# sb-sonata-fpgaio1.net
KiCad netlist of a schematic drawn in Altium Designer
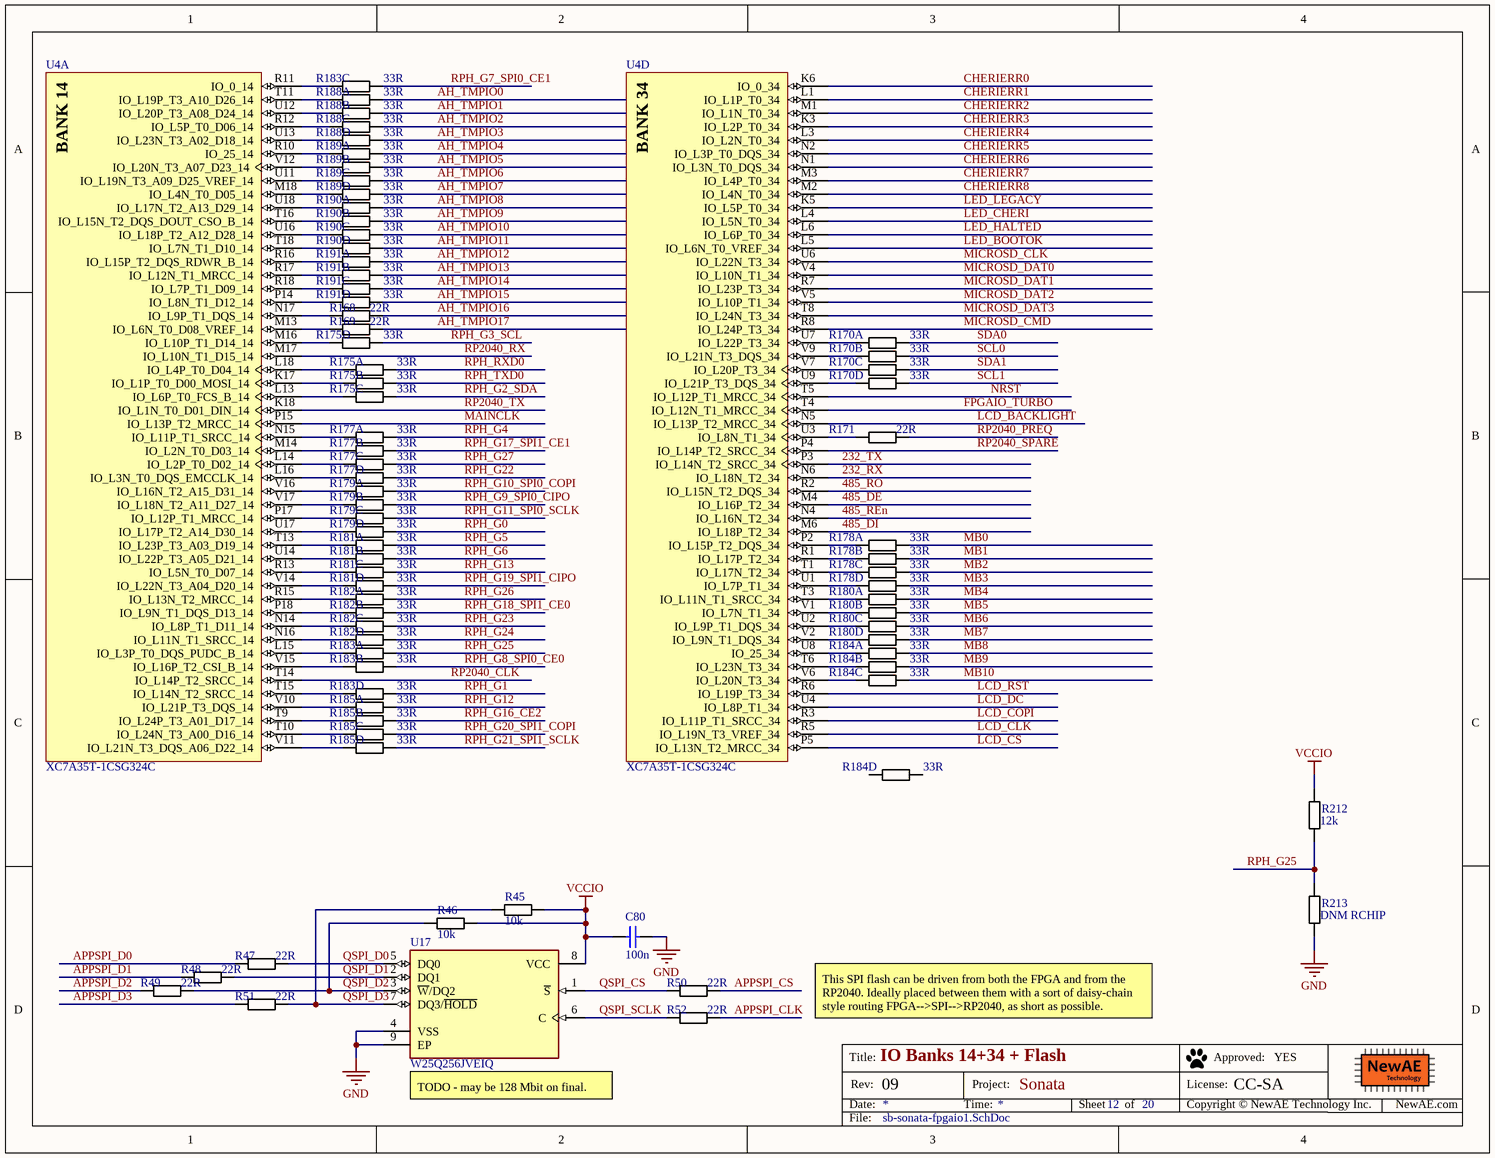
[diagram p0: sb-sonata-fpgaio1.SchDoc]

(export (version "E")
  (design (tool "Eeschema 10.0.6"))
  (components
    (comp (ref "C80")
      (value "100n")
      (footprint "CAPC0402_M")
      (description "100n, 0402")
      (fields (field (name "PART NUMBER") "CCHIP-100n-0402"))
      (libsource (lib "NewAE_AltiumLib") (part "CAP"))
    )
    (comp (ref "R45")
      (value "10k")
      (footprint "RESC1005X40N")
      (description "10k res, 0402, 1%, 1/16W")
      (fields (field (name "PART NUMBER") "RCHIP-10K-0402") (field (name "TOLERANCE") "1%"))
      (libsource (lib "") (part "RES-EU_1"))
    )
    (comp (ref "R46")
      (value "10k")
      (footprint "RESC1005X40N")
      (description "10k res, 0402, 1%, 1/16W")
      (fields (field (name "PART NUMBER") "RCHIP-10K-0402") (field (name "TOLERANCE") "1%"))
      (libsource (lib "") (part "RES-EU_1"))
    )
    (comp (ref "R47")
      (value "22R")
      (footprint "RESC1005X40N")
      (description "22R res, 0402, 1%, 1/16W")
      (fields (field (name "PART NUMBER") "RCHIP-22R-0402") (field (name "TOLERANCE") "1%"))
      (libsource (lib "NewAE_AltiumLib") (part "RES-EU"))
    )
    (comp (ref "R48")
      (value "22R")
      (footprint "RESC1005X40N")
      (description "22R res, 0402, 1%, 1/16W")
      (fields (field (name "PART NUMBER") "RCHIP-22R-0402") (field (name "TOLERANCE") "1%"))
      (libsource (lib "NewAE_AltiumLib") (part "RES-EU"))
    )
    (comp (ref "R49")
      (value "22R")
      (footprint "RESC1005X40N")
      (description "22R res, 0402, 1%, 1/16W")
      (fields (field (name "PART NUMBER") "RCHIP-22R-0402") (field (name "TOLERANCE") "1%"))
      (libsource (lib "NewAE_AltiumLib") (part "RES-EU"))
    )
    (comp (ref "R50")
      (value "22R")
      (footprint "RESC1005X40N")
      (description "22R res, 0402, 1%, 1/16W")
      (fields (field (name "PART NUMBER") "RCHIP-22R-0402") (field (name "TOLERANCE") "1%"))
      (libsource (lib "NewAE_AltiumLib") (part "RES-EU"))
    )
    (comp (ref "R51")
      (value "22R")
      (footprint "RESC1005X40N")
      (description "22R res, 0402, 1%, 1/16W")
      (fields (field (name "PART NUMBER") "RCHIP-22R-0402") (field (name "TOLERANCE") "1%"))
      (libsource (lib "NewAE_AltiumLib") (part "RES-EU"))
    )
    (comp (ref "R52")
      (value "22R")
      (footprint "RESC1005X40N")
      (description "22R res, 0402, 1%, 1/16W")
      (fields (field (name "PART NUMBER") "RCHIP-22R-0402") (field (name "TOLERANCE") "1%"))
      (libsource (lib "NewAE_AltiumLib") (part "RES-EU"))
    )
    (comp (ref "R168")
      (value "22R")
      (footprint "RESC1005X40N")
      (description "22R res, 0402, 1%, 1/16W")
      (fields (field (name "PART NUMBER") "RCHIP-22R-0402") (field (name "TOLERANCE") "1%"))
      (libsource (lib "NewAE_AltiumLib") (part "RES-EU"))
    )
    (comp (ref "R169")
      (value "22R")
      (footprint "RESC1005X40N")
      (description "22R res, 0402, 1%, 1/16W")
      (fields (field (name "PART NUMBER") "RCHIP-22R-0402") (field (name "TOLERANCE") "1%"))
      (libsource (lib "NewAE_AltiumLib") (part "RES-EU"))
    )
    (comp (ref "R170")
      (value "33R")
      (footprint "741C083")
      (description "33-ohm, 0.5mm res array")
      (fields (field (name "PART NUMBER") "741C083330JP"))
      (libsource (lib "NewAE_AltiumLib") (part "RES-EU-4ARRAY"))
    )
    (comp (ref "R171")
      (value "22R")
      (footprint "RESC1005X40N")
      (description "22R res, 0402, 1%, 1/16W")
      (fields (field (name "PART NUMBER") "RCHIP-22R-0402") (field (name "TOLERANCE") "1%"))
      (libsource (lib "NewAE_AltiumLib") (part "RES-EU"))
    )
    (comp (ref "R175")
      (value "33R")
      (footprint "741C083")
      (description "33-ohm, 0.5mm res array")
      (fields (field (name "PART NUMBER") "741C083330JP"))
      (libsource (lib "NewAE_AltiumLib") (part "RES-EU-4ARRAY"))
    )
    (comp (ref "R177")
      (value "33R")
      (footprint "741C083")
      (description "33-ohm, 0.5mm res array")
      (fields (field (name "PART NUMBER") "741C083330JP"))
      (libsource (lib "NewAE_AltiumLib") (part "RES-EU-4ARRAY"))
    )
    (comp (ref "R178")
      (value "33R")
      (footprint "741C083")
      (description "33-ohm, 0.5mm res array")
      (fields (field (name "PART NUMBER") "741C083330JP"))
      (libsource (lib "NewAE_AltiumLib") (part "RES-EU-4ARRAY"))
    )
    (comp (ref "R179")
      (value "33R")
      (footprint "741C083")
      (description "33-ohm, 0.5mm res array")
      (fields (field (name "PART NUMBER") "741C083330JP"))
      (libsource (lib "NewAE_AltiumLib") (part "RES-EU-4ARRAY"))
    )
    (comp (ref "R180")
      (value "33R")
      (footprint "741C083")
      (description "33-ohm, 0.5mm res array")
      (fields (field (name "PART NUMBER") "741C083330JP"))
      (libsource (lib "NewAE_AltiumLib") (part "RES-EU-4ARRAY"))
    )
    (comp (ref "R181")
      (value "33R")
      (footprint "741C083")
      (description "33-ohm, 0.5mm res array")
      (fields (field (name "PART NUMBER") "741C083330JP"))
      (libsource (lib "NewAE_AltiumLib") (part "RES-EU-4ARRAY"))
    )
    (comp (ref "R182")
      (value "33R")
      (footprint "741C083")
      (description "33-ohm, 0.5mm res array")
      (fields (field (name "PART NUMBER") "741C083330JP"))
      (libsource (lib "NewAE_AltiumLib") (part "RES-EU-4ARRAY"))
    )
    (comp (ref "R183")
      (value "33R")
      (footprint "741C083")
      (description "33-ohm, 0.5mm res array")
      (fields (field (name "PART NUMBER") "741C083330JP"))
      (libsource (lib "NewAE_AltiumLib") (part "RES-EU-4ARRAY"))
    )
    (comp (ref "R184")
      (value "33R")
      (footprint "741C083")
      (description "33-ohm, 0.5mm res array")
      (fields (field (name "PART NUMBER") "741C083330JP"))
      (libsource (lib "NewAE_AltiumLib") (part "RES-EU-4ARRAY"))
    )
    (comp (ref "R185")
      (value "33R")
      (footprint "741C083")
      (description "33-ohm, 0.5mm res array")
      (fields (field (name "PART NUMBER") "741C083330JP"))
      (libsource (lib "NewAE_AltiumLib") (part "RES-EU-4ARRAY"))
    )
    (comp (ref "R188")
      (value "33R")
      (footprint "741C083")
      (description "33-ohm, 0.5mm res array")
      (fields (field (name "PART NUMBER") "741C083330JP"))
      (libsource (lib "NewAE_AltiumLib") (part "RES-EU-4ARRAY"))
    )
    (comp (ref "R189")
      (value "33R")
      (footprint "741C083")
      (description "33-ohm, 0.5mm res array")
      (fields (field (name "PART NUMBER") "741C083330JP"))
      (libsource (lib "NewAE_AltiumLib") (part "RES-EU-4ARRAY"))
    )
    (comp (ref "R190")
      (value "33R")
      (footprint "741C083")
      (description "33-ohm, 0.5mm res array")
      (fields (field (name "PART NUMBER") "741C083330JP"))
      (libsource (lib "NewAE_AltiumLib") (part "RES-EU-4ARRAY"))
    )
    (comp (ref "R191")
      (value "33R")
      (footprint "741C083")
      (description "33-ohm, 0.5mm res array")
      (fields (field (name "PART NUMBER") "741C083330JP"))
      (libsource (lib "NewAE_AltiumLib") (part "RES-EU-4ARRAY"))
    )
    (comp (ref "R212")
      (value "12k")
      (footprint "RESC1608X55N")
      (description "12k res, 0603, 1%, 1/10W")
      (fields (field (name "PART NUMBER") "RCHIP-12K-0603") (field (name "TOLERANCE") "1%"))
      (libsource (lib "") (part "RES-EU_2"))
    )
    (comp (ref "R213")
      (value "DNM RCHIP")
      (footprint "RESC1608X55N")
      (description "Do Not Mount Resistor")
      (fields (field (name "PART NUMBER") "RCHIP-DNM-0603"))
      (libsource (lib "") (part "RES-EU_2"))
    )
    (comp (ref "U4")
      (value "XC7A35T-1CSG324C")
      (footprint "CSG324")
      (description "Artix-7 FPGA, 210 User I/Os, 0 GTP, 324-Ball BGA, Speed Grade 1, Commercial Grade, Pb-Free")
      (fields (field (name "MANUFACTURER") "Xilinx"))
      (libsource (lib "") (part "XLNX-XC7A35T-CSG324_1"))
    )
    (comp (ref "U17")
      (value "W25Q256JVEIQ")
      (footprint "WSON68_Micron")
      (description "IC FLASH 256M SPI 133MHZ 8WPDFN")
      (libsource (lib "NewAE_AltiumLib") (part "QSPI_WSON"))
    )
  )
  (nets
    (net (code "1") (name "/232_RX") (class "Default")
      (node (ref "U4") (pin "N6") (pinfunction "IO_L18N_T2_34_N6") (pintype "bidirectional"))
    )
    (net (code "2") (name "/232_TX") (class "Default")
      (node (ref "U4") (pin "P3") (pinfunction "IO_L14N_T2_SRCC_34_P3") (pintype "bidirectional"))
    )
    (net (code "3") (name "/485_DE") (class "Default")
      (node (ref "U4") (pin "M4") (pinfunction "IO_L16P_T2_34_M4") (pintype "bidirectional"))
    )
    (net (code "4") (name "/485_DI") (class "Default")
      (node (ref "U4") (pin "M6") (pinfunction "IO_L18P_T2_34_M6") (pintype "bidirectional"))
    )
    (net (code "5") (name "/485_REn") (class "Default")
      (node (ref "U4") (pin "N4") (pinfunction "IO_L16N_T2_34_N4") (pintype "bidirectional"))
    )
    (net (code "6") (name "/485_RO") (class "Default")
      (node (ref "U4") (pin "R2") (pinfunction "IO_L15N_T2_DQS_34_R2") (pintype "bidirectional"))
    )
    (net (code "7") (name "/AH_TMPIO0") (class "Default")
      (node (ref "R188") (pin "1B") (pinfunction "1B_1B") (pintype "passive"))
    )
    (net (code "8") (name "/AH_TMPIO1") (class "Default")
      (node (ref "R188") (pin "2B") (pinfunction "2B_2B") (pintype "passive"))
    )
    (net (code "9") (name "/AH_TMPIO2") (class "Default")
      (node (ref "R188") (pin "3B") (pinfunction "3B_3B") (pintype "passive"))
    )
    (net (code "10") (name "/AH_TMPIO3") (class "Default")
      (node (ref "R188") (pin "4B") (pinfunction "4B_4B") (pintype "passive"))
    )
    (net (code "11") (name "/AH_TMPIO4") (class "Default")
      (node (ref "R189") (pin "1B") (pinfunction "1B_1B") (pintype "passive"))
    )
    (net (code "12") (name "/AH_TMPIO5") (class "Default")
      (node (ref "R189") (pin "2B") (pinfunction "2B_2B") (pintype "passive"))
    )
    (net (code "13") (name "/AH_TMPIO6") (class "Default")
      (node (ref "R189") (pin "3B") (pinfunction "3B_3B") (pintype "passive"))
    )
    (net (code "14") (name "/AH_TMPIO7") (class "Default")
      (node (ref "R189") (pin "4B") (pinfunction "4B_4B") (pintype "passive"))
    )
    (net (code "15") (name "/AH_TMPIO8") (class "Default")
      (node (ref "R190") (pin "1B") (pinfunction "1B_1B") (pintype "passive"))
    )
    (net (code "16") (name "/AH_TMPIO9") (class "Default")
      (node (ref "R190") (pin "2B") (pinfunction "2B_2B") (pintype "passive"))
    )
    (net (code "17") (name "/AH_TMPIO10") (class "Default")
      (node (ref "R190") (pin "3B") (pinfunction "3B_3B") (pintype "passive"))
    )
    (net (code "18") (name "/AH_TMPIO11") (class "Default")
      (node (ref "R190") (pin "4B") (pinfunction "4B_4B") (pintype "passive"))
    )
    (net (code "19") (name "/AH_TMPIO12") (class "Default")
      (node (ref "R191") (pin "1B") (pinfunction "1B_1B") (pintype "passive"))
    )
    (net (code "20") (name "/AH_TMPIO13") (class "Default")
      (node (ref "R191") (pin "2B") (pinfunction "2B_2B") (pintype "passive"))
    )
    (net (code "21") (name "/AH_TMPIO14") (class "Default")
      (node (ref "R191") (pin "3B") (pinfunction "3B_3B") (pintype "passive"))
    )
    (net (code "22") (name "/AH_TMPIO15") (class "Default")
      (node (ref "R191") (pin "4B") (pinfunction "4B_4B") (pintype "passive"))
    )
    (net (code "23") (name "/AH_TMPIO16") (class "Default")
      (node (ref "R168") (pin "2") (pinfunction "2_2") (pintype "passive"))
    )
    (net (code "24") (name "/AH_TMPIO17") (class "Default")
      (node (ref "R169") (pin "2") (pinfunction "2_2") (pintype "passive"))
    )
    (net (code "25") (name "/APPSPI_CLK") (class "Default")
      (node (ref "R52") (pin "2") (pinfunction "2_2") (pintype "passive"))
    )
    (net (code "26") (name "/APPSPI_CS") (class "Default")
      (node (ref "R50") (pin "2") (pinfunction "2_2") (pintype "passive"))
    )
    (net (code "27") (name "/APPSPI_D0") (class "Default")
      (node (ref "R47") (pin "1") (pinfunction "1_1") (pintype "passive"))
    )
    (net (code "28") (name "/APPSPI_D1") (class "Default")
      (node (ref "R48") (pin "1") (pinfunction "1_1") (pintype "passive"))
    )
    (net (code "29") (name "/APPSPI_D2") (class "Default")
      (node (ref "R49") (pin "1") (pinfunction "1_1") (pintype "passive"))
    )
    (net (code "30") (name "/APPSPI_D3") (class "Default")
      (node (ref "R51") (pin "1") (pinfunction "1_1") (pintype "passive"))
    )
    (net (code "31") (name "/CHERIERR0") (class "Default")
      (node (ref "U4") (pin "K6") (pinfunction "IO_0_34_K6") (pintype "bidirectional"))
    )
    (net (code "32") (name "/CHERIERR1") (class "Default")
      (node (ref "U4") (pin "L1") (pinfunction "IO_L1P_T0_34_L1") (pintype "bidirectional"))
    )
    (net (code "33") (name "/CHERIERR2") (class "Default")
      (node (ref "U4") (pin "M1") (pinfunction "IO_L1N_T0_34_M1") (pintype "bidirectional"))
    )
    (net (code "34") (name "/CHERIERR3") (class "Default")
      (node (ref "U4") (pin "K3") (pinfunction "IO_L2P_T0_34_K3") (pintype "bidirectional"))
    )
    (net (code "35") (name "/CHERIERR4") (class "Default")
      (node (ref "U4") (pin "L3") (pinfunction "IO_L2N_T0_34_L3") (pintype "bidirectional"))
    )
    (net (code "36") (name "/CHERIERR5") (class "Default")
      (node (ref "U4") (pin "N2") (pinfunction "IO_L3P_T0_DQS_34_N2") (pintype "bidirectional"))
    )
    (net (code "37") (name "/CHERIERR6") (class "Default")
      (node (ref "U4") (pin "N1") (pinfunction "IO_L3N_T0_DQS_34_N1") (pintype "bidirectional"))
    )
    (net (code "38") (name "/CHERIERR7") (class "Default")
      (node (ref "U4") (pin "M3") (pinfunction "IO_L4P_T0_34_M3") (pintype "bidirectional"))
    )
    (net (code "39") (name "/CHERIERR8") (class "Default")
      (node (ref "U4") (pin "M2") (pinfunction "IO_L4N_T0_34_M2") (pintype "bidirectional"))
    )
    (net (code "40") (name "/FPGAIO_TURBO") (class "Default")
      (node (ref "U4") (pin "T4") (pinfunction "IO_L12N_T1_MRCC_34_T4") (pintype "bidirectional"))
    )
    (net (code "41") (name "/LCD_BACKLIGHT") (class "Default")
      (node (ref "U4") (pin "N5") (pinfunction "IO_L13P_T2_MRCC_34_N5") (pintype "bidirectional"))
    )
    (net (code "42") (name "/LCD_CLK") (class "Default")
      (node (ref "U4") (pin "R5") (pinfunction "IO_L19N_T3_VREF_34_R5") (pintype "bidirectional"))
    )
    (net (code "43") (name "/LCD_COPI") (class "Default")
      (node (ref "U4") (pin "R3") (pinfunction "IO_L11P_T1_SRCC_34_R3") (pintype "bidirectional"))
    )
    (net (code "44") (name "/LCD_CS") (class "Default")
      (node (ref "U4") (pin "P5") (pinfunction "IO_L13N_T2_MRCC_34_P5") (pintype "bidirectional"))
    )
    (net (code "45") (name "/LCD_DC") (class "Default")
      (node (ref "U4") (pin "U4") (pinfunction "IO_L8P_T1_34_U4") (pintype "bidirectional"))
    )
    (net (code "46") (name "/LCD_RST") (class "Default")
      (node (ref "U4") (pin "R6") (pinfunction "IO_L19P_T3_34_R6") (pintype "bidirectional"))
    )
    (net (code "47") (name "/LED_BOOTOK") (class "Default")
      (node (ref "U4") (pin "L5") (pinfunction "IO_L6N_T0_VREF_34_L5") (pintype "bidirectional"))
    )
    (net (code "48") (name "/LED_CHERI") (class "Default")
      (node (ref "U4") (pin "L4") (pinfunction "IO_L5N_T0_34_L4") (pintype "bidirectional"))
    )
    (net (code "49") (name "/LED_HALTED") (class "Default")
      (node (ref "U4") (pin "L6") (pinfunction "IO_L6P_T0_34_L6") (pintype "bidirectional"))
    )
    (net (code "50") (name "/LED_LEGACY") (class "Default")
      (node (ref "U4") (pin "K5") (pinfunction "IO_L5P_T0_34_K5") (pintype "bidirectional"))
    )
    (net (code "51") (name "/MAINCLK") (class "Default")
      (node (ref "U4") (pin "P15") (pinfunction "IO_L13P_T2_MRCC_14_P15") (pintype "bidirectional"))
    )
    (net (code "52") (name "/MB0") (class "Default")
      (node (ref "R178") (pin "1B") (pinfunction "1B_1B") (pintype "passive"))
    )
    (net (code "53") (name "/MB1") (class "Default")
      (node (ref "R178") (pin "2B") (pinfunction "2B_2B") (pintype "passive"))
    )
    (net (code "54") (name "/MB2") (class "Default")
      (node (ref "R178") (pin "3B") (pinfunction "3B_3B") (pintype "passive"))
    )
    (net (code "55") (name "/MB3") (class "Default")
      (node (ref "R178") (pin "4B") (pinfunction "4B_4B") (pintype "passive"))
    )
    (net (code "56") (name "/MB4") (class "Default")
      (node (ref "R180") (pin "1B") (pinfunction "1B_1B") (pintype "passive"))
    )
    (net (code "57") (name "/MB5") (class "Default")
      (node (ref "R180") (pin "2B") (pinfunction "2B_2B") (pintype "passive"))
    )
    (net (code "58") (name "/MB6") (class "Default")
      (node (ref "R180") (pin "3B") (pinfunction "3B_3B") (pintype "passive"))
    )
    (net (code "59") (name "/MB7") (class "Default")
      (node (ref "R180") (pin "4B") (pinfunction "4B_4B") (pintype "passive"))
    )
    (net (code "60") (name "/MB8") (class "Default")
      (node (ref "R184") (pin "1B") (pinfunction "1B_1B") (pintype "passive"))
    )
    (net (code "61") (name "/MB9") (class "Default")
      (node (ref "R184") (pin "2B") (pinfunction "2B_2B") (pintype "passive"))
    )
    (net (code "62") (name "/MB10") (class "Default")
      (node (ref "R184") (pin "3B") (pinfunction "3B_3B") (pintype "passive"))
    )
    (net (code "63") (name "/MICROSD_CLK") (class "Default")
      (node (ref "U4") (pin "U6") (pinfunction "IO_L22N_T3_34_U6") (pintype "bidirectional"))
    )
    (net (code "64") (name "/MICROSD_CMD") (class "Default")
      (node (ref "U4") (pin "R8") (pinfunction "IO_L24P_T3_34_R8") (pintype "bidirectional"))
    )
    (net (code "65") (name "/MICROSD_DAT0") (class "Default")
      (node (ref "U4") (pin "V4") (pinfunction "IO_L10N_T1_34_V4") (pintype "bidirectional"))
    )
    (net (code "66") (name "/MICROSD_DAT1") (class "Default")
      (node (ref "U4") (pin "R7") (pinfunction "IO_L23P_T3_34_R7") (pintype "bidirectional"))
    )
    (net (code "67") (name "/MICROSD_DAT2") (class "Default")
      (node (ref "U4") (pin "V5") (pinfunction "IO_L10P_T1_34_V5") (pintype "bidirectional"))
    )
    (net (code "68") (name "/MICROSD_DAT3") (class "Default")
      (node (ref "U4") (pin "T8") (pinfunction "IO_L24N_T3_34_T8") (pintype "bidirectional"))
    )
    (net (code "69") (name "/NRST") (class "Default")
      (node (ref "U4") (pin "T5") (pinfunction "IO_L12P_T1_MRCC_34_T5") (pintype "bidirectional"))
    )
    (net (code "70") (name "/QSPI_CS") (class "Default")
      (node (ref "R50") (pin "1") (pinfunction "1_1") (pintype "passive"))
      (node (ref "U17") (pin "1") (pinfunction "~{S}_1") (pintype "input"))
    )
    (net (code "71") (name "/QSPI_D0") (class "Default")
      (node (ref "R47") (pin "2") (pinfunction "2_2") (pintype "passive"))
      (node (ref "U17") (pin "5") (pinfunction "DQ0_5") (pintype "bidirectional"))
    )
    (net (code "72") (name "/QSPI_D1") (class "Default")
      (node (ref "R48") (pin "2") (pinfunction "2_2") (pintype "passive"))
      (node (ref "U17") (pin "2") (pinfunction "DQ1_2") (pintype "bidirectional"))
    )
    (net (code "73") (name "/QSPI_D2") (class "Default")
      (node (ref "R46") (pin "2") (pinfunction "2_2") (pintype "passive"))
      (node (ref "R49") (pin "2") (pinfunction "2_2") (pintype "passive"))
      (node (ref "U17") (pin "3") (pinfunction "~{W}/DQ2_3") (pintype "bidirectional"))
    )
    (net (code "74") (name "/QSPI_D3") (class "Default")
      (node (ref "R45") (pin "2") (pinfunction "2_2") (pintype "passive"))
      (node (ref "R51") (pin "2") (pinfunction "2_2") (pintype "passive"))
      (node (ref "U17") (pin "7") (pinfunction "DQ3/~{HOLD}_7") (pintype "bidirectional"))
    )
    (net (code "75") (name "/QSPI_SCLK") (class "Default")
      (node (ref "R52") (pin "1") (pinfunction "1_1") (pintype "passive"))
      (node (ref "U17") (pin "6") (pinfunction "C_6") (pintype "input"))
    )
    (net (code "76") (name "/RP2040_CLK") (class "Default")
      (node (ref "U4") (pin "T14") (pinfunction "IO_L14P_T2_SRCC_14_T14") (pintype "bidirectional"))
    )
    (net (code "77") (name "/RP2040_PREQ") (class "Default")
      (node (ref "R171") (pin "2") (pinfunction "2_2") (pintype "passive"))
    )
    (net (code "78") (name "/RP2040_RX") (class "Default")
      (node (ref "U4") (pin "M17") (pinfunction "IO_L10N_T1_D15_14_M17") (pintype "bidirectional"))
    )
    (net (code "79") (name "/RP2040_SPARE") (class "Default")
      (node (ref "U4") (pin "P4") (pinfunction "IO_L14P_T2_SRCC_34_P4") (pintype "bidirectional"))
    )
    (net (code "80") (name "/RP2040_TX") (class "Default")
      (node (ref "U4") (pin "K18") (pinfunction "IO_L1N_T0_D01_DIN_14_K18") (pintype "bidirectional"))
    )
    (net (code "81") (name "/RPH_G0") (class "Default")
      (node (ref "R179") (pin "4B") (pinfunction "4B_4B") (pintype "passive"))
    )
    (net (code "82") (name "/RPH_G1") (class "Default")
      (node (ref "R183") (pin "4B") (pinfunction "4B_4B") (pintype "passive"))
    )
    (net (code "83") (name "/RPH_G2_SDA") (class "Default")
      (node (ref "R175") (pin "3B") (pinfunction "3B_3B") (pintype "passive"))
    )
    (net (code "84") (name "/RPH_G3_SCL") (class "Default")
      (node (ref "R175") (pin "4B") (pinfunction "4B_4B") (pintype "passive"))
    )
    (net (code "85") (name "/RPH_G4") (class "Default")
      (node (ref "R177") (pin "1B") (pinfunction "1B_1B") (pintype "passive"))
    )
    (net (code "86") (name "/RPH_G5") (class "Default")
      (node (ref "R181") (pin "1B") (pinfunction "1B_1B") (pintype "passive"))
    )
    (net (code "87") (name "/RPH_G6") (class "Default")
      (node (ref "R181") (pin "2B") (pinfunction "2B_2B") (pintype "passive"))
    )
    (net (code "88") (name "/RPH_G7_SPI0_CE1") (class "Default")
      (node (ref "R183") (pin "3B") (pinfunction "3B_3B") (pintype "passive"))
    )
    (net (code "89") (name "/RPH_G8_SPI0_CE0") (class "Default")
      (node (ref "R183") (pin "2B") (pinfunction "2B_2B") (pintype "passive"))
    )
    (net (code "90") (name "/RPH_G9_SPI0_CIPO") (class "Default")
      (node (ref "R179") (pin "2B") (pinfunction "2B_2B") (pintype "passive"))
    )
    (net (code "91") (name "/RPH_G10_SPI0_COPI") (class "Default")
      (node (ref "R179") (pin "1B") (pinfunction "1B_1B") (pintype "passive"))
    )
    (net (code "92") (name "/RPH_G11_SPI0_SCLK") (class "Default")
      (node (ref "R179") (pin "3B") (pinfunction "3B_3B") (pintype "passive"))
    )
    (net (code "93") (name "/RPH_G12") (class "Default")
      (node (ref "R185") (pin "1B") (pinfunction "1B_1B") (pintype "passive"))
    )
    (net (code "94") (name "/RPH_G13") (class "Default")
      (node (ref "R181") (pin "3B") (pinfunction "3B_3B") (pintype "passive"))
    )
    (net (code "95") (name "/RPH_G16_CE2") (class "Default")
      (node (ref "R185") (pin "2B") (pinfunction "2B_2B") (pintype "passive"))
    )
    (net (code "96") (name "/RPH_G17_SPI1_CE1") (class "Default")
      (node (ref "R177") (pin "2B") (pinfunction "2B_2B") (pintype "passive"))
    )
    (net (code "97") (name "/RPH_G18_SPI1_CE0") (class "Default")
      (node (ref "R182") (pin "2B") (pinfunction "2B_2B") (pintype "passive"))
    )
    (net (code "98") (name "/RPH_G19_SPI1_CIPO") (class "Default")
      (node (ref "R181") (pin "4B") (pinfunction "4B_4B") (pintype "passive"))
    )
    (net (code "99") (name "/RPH_G20_SPI1_COPI") (class "Default")
      (node (ref "R185") (pin "3B") (pinfunction "3B_3B") (pintype "passive"))
    )
    (net (code "100") (name "/RPH_G21_SPI1_SCLK") (class "Default")
      (node (ref "R185") (pin "4B") (pinfunction "4B_4B") (pintype "passive"))
    )
    (net (code "101") (name "/RPH_G22") (class "Default")
      (node (ref "R177") (pin "4B") (pinfunction "4B_4B") (pintype "passive"))
    )
    (net (code "102") (name "/RPH_G23") (class "Default")
      (node (ref "R182") (pin "3B") (pinfunction "3B_3B") (pintype "passive"))
    )
    (net (code "103") (name "/RPH_G24") (class "Default")
      (node (ref "R182") (pin "4B") (pinfunction "4B_4B") (pintype "passive"))
    )
    (net (code "104") (name "/RPH_G25") (class "Default")
      (node (ref "R183") (pin "1B") (pinfunction "1B_1B") (pintype "passive"))
      (node (ref "R212") (pin "1") (pinfunction "1_1") (pintype "passive"))
      (node (ref "R213") (pin "2") (pinfunction "2_2") (pintype "passive"))
    )
    (net (code "105") (name "/RPH_G26") (class "Default")
      (node (ref "R182") (pin "1B") (pinfunction "1B_1B") (pintype "passive"))
    )
    (net (code "106") (name "/RPH_G27") (class "Default")
      (node (ref "R177") (pin "3B") (pinfunction "3B_3B") (pintype "passive"))
    )
    (net (code "107") (name "/RPH_RXD0") (class "Default")
      (node (ref "R175") (pin "1B") (pinfunction "1B_1B") (pintype "passive"))
    )
    (net (code "108") (name "/RPH_TXD0") (class "Default")
      (node (ref "R175") (pin "2B") (pinfunction "2B_2B") (pintype "passive"))
    )
    (net (code "109") (name "/SCL0") (class "Default")
      (node (ref "R170") (pin "2B") (pinfunction "2B_2B") (pintype "passive"))
    )
    (net (code "110") (name "/SCL1") (class "Default")
      (node (ref "R170") (pin "4B") (pinfunction "4B_4B") (pintype "passive"))
    )
    (net (code "111") (name "/SDA0") (class "Default")
      (node (ref "R170") (pin "1B") (pinfunction "1B_1B") (pintype "passive"))
    )
    (net (code "112") (name "/SDA1") (class "Default")
      (node (ref "R170") (pin "3B") (pinfunction "3B_3B") (pintype "passive"))
    )
    (net (code "113") (name "GND") (class "Default")
      (node (ref "C80") (pin "2") (pinfunction "2_2") (pintype "passive"))
      (node (ref "R213") (pin "1") (pinfunction "1_1") (pintype "passive"))
      (node (ref "U17") (pin "4") (pinfunction "VSS_4") (pintype "power_in"))
      (node (ref "U17") (pin "9") (pinfunction "EP_9") (pintype "power_in"))
    )
    (net (code "114") (name "Net-(U4A-IO_0_14)") (class "Default")
      (node (ref "R183") (pin "3A") (pinfunction "3A_3A") (pintype "passive"))
      (node (ref "U4") (pin "R11") (pinfunction "IO_0_14_R11") (pintype "bidirectional"))
    )
    (net (code "115") (name "Net-(U4A-IO_25_14)") (class "Default")
      (node (ref "R189") (pin "1A") (pinfunction "1A_1A") (pintype "passive"))
      (node (ref "U4") (pin "R10") (pinfunction "IO_25_14_R10") (pintype "bidirectional"))
    )
    (net (code "116") (name "Net-(U4A-IO_L1P_T0_D00_MOSI_14)") (class "Default")
      (node (ref "R175") (pin "2A") (pinfunction "2A_2A") (pintype "passive"))
      (node (ref "U4") (pin "K17") (pinfunction "IO_L1P_T0_D00_MOSI_14_K17") (pintype "bidirectional"))
    )
    (net (code "117") (name "Net-(U4A-IO_L2N_T0_D03_14)") (class "Default")
      (node (ref "R177") (pin "2A") (pinfunction "2A_2A") (pintype "passive"))
      (node (ref "U4") (pin "M14") (pinfunction "IO_L2N_T0_D03_14_M14") (pintype "bidirectional"))
    )
    (net (code "118") (name "Net-(U4A-IO_L2P_T0_D02_14)") (class "Default")
      (node (ref "R177") (pin "3A") (pinfunction "3A_3A") (pintype "passive"))
      (node (ref "U4") (pin "L14") (pinfunction "IO_L2P_T0_D02_14_L14") (pintype "bidirectional"))
    )
    (net (code "119") (name "Net-(U4A-IO_L3N_T0_DQS_EMCCLK_14)") (class "Default")
      (node (ref "R177") (pin "4A") (pinfunction "4A_4A") (pintype "passive"))
      (node (ref "U4") (pin "L16") (pinfunction "IO_L3N_T0_DQS_EMCCLK_14_L16") (pintype "bidirectional"))
    )
    (net (code "120") (name "Net-(U4A-IO_L3P_T0_DQS_PUDC_B_14)") (class "Default")
      (node (ref "R183") (pin "1A") (pinfunction "1A_1A") (pintype "passive"))
      (node (ref "U4") (pin "L15") (pinfunction "IO_L3P_T0_DQS_PUDC_B_14_L15") (pintype "bidirectional"))
    )
    (net (code "121") (name "Net-(U4A-IO_L4N_T0_D05_14)") (class "Default")
      (node (ref "R189") (pin "4A") (pinfunction "4A_4A") (pintype "passive"))
      (node (ref "U4") (pin "M18") (pinfunction "IO_L4N_T0_D05_14_M18") (pintype "bidirectional"))
    )
    (net (code "122") (name "Net-(U4A-IO_L4P_T0_D04_14)") (class "Default")
      (node (ref "R175") (pin "1A") (pinfunction "1A_1A") (pintype "passive"))
      (node (ref "U4") (pin "L18") (pinfunction "IO_L4P_T0_D04_14_L18") (pintype "bidirectional"))
    )
    (net (code "123") (name "Net-(U4A-IO_L5N_T0_D07_14)") (class "Default")
      (node (ref "R181") (pin "3A") (pinfunction "3A_3A") (pintype "passive"))
      (node (ref "U4") (pin "R13") (pinfunction "IO_L5N_T0_D07_14_R13") (pintype "bidirectional"))
    )
    (net (code "124") (name "Net-(U4A-IO_L5P_T0_D06_14)") (class "Default")
      (node (ref "R188") (pin "3A") (pinfunction "3A_3A") (pintype "passive"))
      (node (ref "U4") (pin "R12") (pinfunction "IO_L5P_T0_D06_14_R12") (pintype "bidirectional"))
    )
    (net (code "125") (name "Net-(U4A-IO_L6N_T0_D08_VREF_14)") (class "Default")
      (node (ref "R169") (pin "1") (pinfunction "1_1") (pintype "passive"))
      (node (ref "U4") (pin "M13") (pinfunction "IO_L6N_T0_D08_VREF_14_M13") (pintype "bidirectional"))
    )
    (net (code "126") (name "Net-(U4A-IO_L6P_T0_FCS_B_14)") (class "Default")
      (node (ref "R175") (pin "3A") (pinfunction "3A_3A") (pintype "passive"))
      (node (ref "U4") (pin "L13") (pinfunction "IO_L6P_T0_FCS_B_14_L13") (pintype "bidirectional"))
    )
    (net (code "127") (name "Net-(U4A-IO_L7N_T1_D10_14)") (class "Default")
      (node (ref "R190") (pin "4A") (pinfunction "4A_4A") (pintype "passive"))
      (node (ref "U4") (pin "T18") (pinfunction "IO_L7N_T1_D10_14_T18") (pintype "bidirectional"))
    )
    (net (code "128") (name "Net-(U4A-IO_L7P_T1_D09_14)") (class "Default")
      (node (ref "R191") (pin "3A") (pinfunction "3A_3A") (pintype "passive"))
      (node (ref "U4") (pin "R18") (pinfunction "IO_L7P_T1_D09_14_R18") (pintype "bidirectional"))
    )
    (net (code "129") (name "Net-(U4A-IO_L8N_T1_D12_14)") (class "Default")
      (node (ref "R191") (pin "4A") (pinfunction "4A_4A") (pintype "passive"))
      (node (ref "U4") (pin "P14") (pinfunction "IO_L8N_T1_D12_14_P14") (pintype "bidirectional"))
    )
    (net (code "130") (name "Net-(U4A-IO_L8P_T1_D11_14)") (class "Default")
      (node (ref "R182") (pin "3A") (pinfunction "3A_3A") (pintype "passive"))
      (node (ref "U4") (pin "N14") (pinfunction "IO_L8P_T1_D11_14_N14") (pintype "bidirectional"))
    )
    (net (code "131") (name "Net-(U4A-IO_L9N_T1_DQS_D13_14)") (class "Default")
      (node (ref "R182") (pin "2A") (pinfunction "2A_2A") (pintype "passive"))
      (node (ref "U4") (pin "P18") (pinfunction "IO_L9N_T1_DQS_D13_14_P18") (pintype "bidirectional"))
    )
    (net (code "132") (name "Net-(U4A-IO_L9P_T1_DQS_14)") (class "Default")
      (node (ref "R168") (pin "1") (pinfunction "1_1") (pintype "passive"))
      (node (ref "U4") (pin "N17") (pinfunction "IO_L9P_T1_DQS_14_N17") (pintype "bidirectional"))
    )
    (net (code "133") (name "Net-(U4A-IO_L10P_T1_D14_14)") (class "Default")
      (node (ref "R175") (pin "4A") (pinfunction "4A_4A") (pintype "passive"))
      (node (ref "U4") (pin "M16") (pinfunction "IO_L10P_T1_D14_14_M16") (pintype "bidirectional"))
    )
    (net (code "134") (name "Net-(U4A-IO_L11N_T1_SRCC_14)") (class "Default")
      (node (ref "R182") (pin "4A") (pinfunction "4A_4A") (pintype "passive"))
      (node (ref "U4") (pin "N16") (pinfunction "IO_L11N_T1_SRCC_14_N16") (pintype "bidirectional"))
    )
    (net (code "135") (name "Net-(U4A-IO_L11P_T1_SRCC_14)") (class "Default")
      (node (ref "R177") (pin "1A") (pinfunction "1A_1A") (pintype "passive"))
      (node (ref "U4") (pin "N15") (pinfunction "IO_L11P_T1_SRCC_14_N15") (pintype "bidirectional"))
    )
    (net (code "136") (name "Net-(U4A-IO_L12N_T1_MRCC_14)") (class "Default")
      (node (ref "R191") (pin "2A") (pinfunction "2A_2A") (pintype "passive"))
      (node (ref "U4") (pin "R17") (pinfunction "IO_L12N_T1_MRCC_14_R17") (pintype "bidirectional"))
    )
    (net (code "137") (name "Net-(U4A-IO_L12P_T1_MRCC_14)") (class "Default")
      (node (ref "R179") (pin "3A") (pinfunction "3A_3A") (pintype "passive"))
      (node (ref "U4") (pin "P17") (pinfunction "IO_L12P_T1_MRCC_14_P17") (pintype "bidirectional"))
    )
    (net (code "138") (name "Net-(U4A-IO_L13N_T2_MRCC_14)") (class "Default")
      (node (ref "R182") (pin "1A") (pinfunction "1A_1A") (pintype "passive"))
      (node (ref "U4") (pin "R15") (pinfunction "IO_L13N_T2_MRCC_14_R15") (pintype "bidirectional"))
    )
    (net (code "139") (name "Net-(U4A-IO_L14N_T2_SRCC_14)") (class "Default")
      (node (ref "R183") (pin "4A") (pinfunction "4A_4A") (pintype "passive"))
      (node (ref "U4") (pin "T15") (pinfunction "IO_L14N_T2_SRCC_14_T15") (pintype "bidirectional"))
    )
    (net (code "140") (name "Net-(U4A-IO_L15N_T2_DQS_DOUT_CSO_B_14)") (class "Default")
      (node (ref "R190") (pin "2A") (pinfunction "2A_2A") (pintype "passive"))
      (node (ref "U4") (pin "T16") (pinfunction "IO_L15N_T2_DQS_DOUT_CSO_B_14_T16") (pintype "bidirectional"))
    )
    (net (code "141") (name "Net-(U4A-IO_L15P_T2_DQS_RDWR_B_14)") (class "Default")
      (node (ref "R191") (pin "1A") (pinfunction "1A_1A") (pintype "passive"))
      (node (ref "U4") (pin "R16") (pinfunction "IO_L15P_T2_DQS_RDWR_B_14_R16") (pintype "bidirectional"))
    )
    (net (code "142") (name "Net-(U4A-IO_L16N_T2_A15_D31_14)") (class "Default")
      (node (ref "R179") (pin "1A") (pinfunction "1A_1A") (pintype "passive"))
      (node (ref "U4") (pin "V16") (pinfunction "IO_L16N_T2_A15_D31_14_V16") (pintype "bidirectional"))
    )
    (net (code "143") (name "Net-(U4A-IO_L16P_T2_CSI_B_14)") (class "Default")
      (node (ref "R183") (pin "2A") (pinfunction "2A_2A") (pintype "passive"))
      (node (ref "U4") (pin "V15") (pinfunction "IO_L16P_T2_CSI_B_14_V15") (pintype "bidirectional"))
    )
    (net (code "144") (name "Net-(U4A-IO_L17N_T2_A13_D29_14)") (class "Default")
      (node (ref "R190") (pin "1A") (pinfunction "1A_1A") (pintype "passive"))
      (node (ref "U4") (pin "U18") (pinfunction "IO_L17N_T2_A13_D29_14_U18") (pintype "bidirectional"))
    )
    (net (code "145") (name "Net-(U4A-IO_L17P_T2_A14_D30_14)") (class "Default")
      (node (ref "R179") (pin "4A") (pinfunction "4A_4A") (pintype "passive"))
      (node (ref "U4") (pin "U17") (pinfunction "IO_L17P_T2_A14_D30_14_U17") (pintype "bidirectional"))
    )
    (net (code "146") (name "Net-(U4A-IO_L18N_T2_A11_D27_14)") (class "Default")
      (node (ref "R179") (pin "2A") (pinfunction "2A_2A") (pintype "passive"))
      (node (ref "U4") (pin "V17") (pinfunction "IO_L18N_T2_A11_D27_14_V17") (pintype "bidirectional"))
    )
    (net (code "147") (name "Net-(U4A-IO_L18P_T2_A12_D28_14)") (class "Default")
      (node (ref "R190") (pin "3A") (pinfunction "3A_3A") (pintype "passive"))
      (node (ref "U4") (pin "U16") (pinfunction "IO_L18P_T2_A12_D28_14_U16") (pintype "bidirectional"))
    )
    (net (code "148") (name "Net-(U4A-IO_L19N_T3_A09_D25_VREF_14)") (class "Default")
      (node (ref "R189") (pin "3A") (pinfunction "3A_3A") (pintype "passive"))
      (node (ref "U4") (pin "U11") (pinfunction "IO_L19N_T3_A09_D25_VREF_14_U11") (pintype "bidirectional"))
    )
    (net (code "149") (name "Net-(U4A-IO_L19P_T3_A10_D26_14)") (class "Default")
      (node (ref "R188") (pin "1A") (pinfunction "1A_1A") (pintype "passive"))
      (node (ref "U4") (pin "T11") (pinfunction "IO_L19P_T3_A10_D26_14_T11") (pintype "bidirectional"))
    )
    (net (code "150") (name "Net-(U4A-IO_L20N_T3_A07_D23_14)") (class "Default")
      (node (ref "R189") (pin "2A") (pinfunction "2A_2A") (pintype "passive"))
      (node (ref "U4") (pin "V12") (pinfunction "IO_L20N_T3_A07_D23_14_V12") (pintype "bidirectional"))
    )
    (net (code "151") (name "Net-(U4A-IO_L20P_T3_A08_D24_14)") (class "Default")
      (node (ref "R188") (pin "2A") (pinfunction "2A_2A") (pintype "passive"))
      (node (ref "U4") (pin "U12") (pinfunction "IO_L20P_T3_A08_D24_14_U12") (pintype "bidirectional"))
    )
    (net (code "152") (name "Net-(U4A-IO_L21N_T3_DQS_A06_D22_14)") (class "Default")
      (node (ref "R185") (pin "4A") (pinfunction "4A_4A") (pintype "passive"))
      (node (ref "U4") (pin "V11") (pinfunction "IO_L21N_T3_DQS_A06_D22_14_V11") (pintype "bidirectional"))
    )
    (net (code "153") (name "Net-(U4A-IO_L21P_T3_DQS_14)") (class "Default")
      (node (ref "R185") (pin "1A") (pinfunction "1A_1A") (pintype "passive"))
      (node (ref "U4") (pin "V10") (pinfunction "IO_L21P_T3_DQS_14_V10") (pintype "bidirectional"))
    )
    (net (code "154") (name "Net-(U4A-IO_L22N_T3_A04_D20_14)") (class "Default")
      (node (ref "R181") (pin "4A") (pinfunction "4A_4A") (pintype "passive"))
      (node (ref "U4") (pin "V14") (pinfunction "IO_L22N_T3_A04_D20_14_V14") (pintype "bidirectional"))
    )
    (net (code "155") (name "Net-(U4A-IO_L22P_T3_A05_D21_14)") (class "Default")
      (node (ref "R181") (pin "2A") (pinfunction "2A_2A") (pintype "passive"))
      (node (ref "U4") (pin "U14") (pinfunction "IO_L22P_T3_A05_D21_14_U14") (pintype "bidirectional"))
    )
    (net (code "156") (name "Net-(U4A-IO_L23N_T3_A02_D18_14)") (class "Default")
      (node (ref "R188") (pin "4A") (pinfunction "4A_4A") (pintype "passive"))
      (node (ref "U4") (pin "U13") (pinfunction "IO_L23N_T3_A02_D18_14_U13") (pintype "bidirectional"))
    )
    (net (code "157") (name "Net-(U4A-IO_L23P_T3_A03_D19_14)") (class "Default")
      (node (ref "R181") (pin "1A") (pinfunction "1A_1A") (pintype "passive"))
      (node (ref "U4") (pin "T13") (pinfunction "IO_L23P_T3_A03_D19_14_T13") (pintype "bidirectional"))
    )
    (net (code "158") (name "Net-(U4A-IO_L24N_T3_A00_D16_14)") (class "Default")
      (node (ref "R185") (pin "3A") (pinfunction "3A_3A") (pintype "passive"))
      (node (ref "U4") (pin "T10") (pinfunction "IO_L24N_T3_A00_D16_14_T10") (pintype "bidirectional"))
    )
    (net (code "159") (name "Net-(U4A-IO_L24P_T3_A01_D17_14)") (class "Default")
      (node (ref "R185") (pin "2A") (pinfunction "2A_2A") (pintype "passive"))
      (node (ref "U4") (pin "T9") (pinfunction "IO_L24P_T3_A01_D17_14_T9") (pintype "bidirectional"))
    )
    (net (code "160") (name "Net-(U4D-IO_25_34)") (class "Default")
      (node (ref "R184") (pin "1A") (pinfunction "1A_1A") (pintype "passive"))
      (node (ref "U4") (pin "U8") (pinfunction "IO_25_34_U8") (pintype "bidirectional"))
    )
    (net (code "161") (name "Net-(U4D-IO_L7N_T1_34)") (class "Default")
      (node (ref "R180") (pin "2A") (pinfunction "2A_2A") (pintype "passive"))
      (node (ref "U4") (pin "V1") (pinfunction "IO_L7N_T1_34_V1") (pintype "bidirectional"))
    )
    (net (code "162") (name "Net-(U4D-IO_L7P_T1_34)") (class "Default")
      (node (ref "R178") (pin "4A") (pinfunction "4A_4A") (pintype "passive"))
      (node (ref "U4") (pin "U1") (pinfunction "IO_L7P_T1_34_U1") (pintype "bidirectional"))
    )
    (net (code "163") (name "Net-(U4D-IO_L8N_T1_34)") (class "Default")
      (node (ref "R171") (pin "1") (pinfunction "1_1") (pintype "passive"))
      (node (ref "U4") (pin "U3") (pinfunction "IO_L8N_T1_34_U3") (pintype "bidirectional"))
    )
    (net (code "164") (name "Net-(U4D-IO_L9N_T1_DQS_34)") (class "Default")
      (node (ref "R180") (pin "4A") (pinfunction "4A_4A") (pintype "passive"))
      (node (ref "U4") (pin "V2") (pinfunction "IO_L9N_T1_DQS_34_V2") (pintype "bidirectional"))
    )
    (net (code "165") (name "Net-(U4D-IO_L9P_T1_DQS_34)") (class "Default")
      (node (ref "R180") (pin "3A") (pinfunction "3A_3A") (pintype "passive"))
      (node (ref "U4") (pin "U2") (pinfunction "IO_L9P_T1_DQS_34_U2") (pintype "bidirectional"))
    )
    (net (code "166") (name "Net-(U4D-IO_L11N_T1_SRCC_34)") (class "Default")
      (node (ref "R180") (pin "1A") (pinfunction "1A_1A") (pintype "passive"))
      (node (ref "U4") (pin "T3") (pinfunction "IO_L11N_T1_SRCC_34_T3") (pintype "bidirectional"))
    )
    (net (code "167") (name "Net-(U4D-IO_L15P_T2_DQS_34)") (class "Default")
      (node (ref "R178") (pin "1A") (pinfunction "1A_1A") (pintype "passive"))
      (node (ref "U4") (pin "P2") (pinfunction "IO_L15P_T2_DQS_34_P2") (pintype "bidirectional"))
    )
    (net (code "168") (name "Net-(U4D-IO_L17N_T2_34)") (class "Default")
      (node (ref "R178") (pin "3A") (pinfunction "3A_3A") (pintype "passive"))
      (node (ref "U4") (pin "T1") (pinfunction "IO_L17N_T2_34_T1") (pintype "bidirectional"))
    )
    (net (code "169") (name "Net-(U4D-IO_L17P_T2_34)") (class "Default")
      (node (ref "R178") (pin "2A") (pinfunction "2A_2A") (pintype "passive"))
      (node (ref "U4") (pin "R1") (pinfunction "IO_L17P_T2_34_R1") (pintype "bidirectional"))
    )
    (net (code "170") (name "Net-(U4D-IO_L20N_T3_34)") (class "Default")
      (node (ref "R184") (pin "3A") (pinfunction "3A_3A") (pintype "passive"))
      (node (ref "U4") (pin "V6") (pinfunction "IO_L20N_T3_34_V6") (pintype "bidirectional"))
    )
    (net (code "171") (name "Net-(U4D-IO_L20P_T3_34)") (class "Default")
      (node (ref "R170") (pin "3A") (pinfunction "3A_3A") (pintype "passive"))
      (node (ref "U4") (pin "V7") (pinfunction "IO_L20P_T3_34_V7") (pintype "bidirectional"))
    )
    (net (code "172") (name "Net-(U4D-IO_L21N_T3_DQS_34)") (class "Default")
      (node (ref "R170") (pin "2A") (pinfunction "2A_2A") (pintype "passive"))
      (node (ref "U4") (pin "V9") (pinfunction "IO_L21N_T3_DQS_34_V9") (pintype "bidirectional"))
    )
    (net (code "173") (name "Net-(U4D-IO_L21P_T3_DQS_34)") (class "Default")
      (node (ref "R170") (pin "4A") (pinfunction "4A_4A") (pintype "passive"))
      (node (ref "U4") (pin "U9") (pinfunction "IO_L21P_T3_DQS_34_U9") (pintype "bidirectional"))
    )
    (net (code "174") (name "Net-(U4D-IO_L22P_T3_34)") (class "Default")
      (node (ref "R170") (pin "1A") (pinfunction "1A_1A") (pintype "passive"))
      (node (ref "U4") (pin "U7") (pinfunction "IO_L22P_T3_34_U7") (pintype "bidirectional"))
    )
    (net (code "175") (name "Net-(U4D-IO_L23N_T3_34)") (class "Default")
      (node (ref "R184") (pin "2A") (pinfunction "2A_2A") (pintype "passive"))
      (node (ref "U4") (pin "T6") (pinfunction "IO_L23N_T3_34_T6") (pintype "bidirectional"))
    )
    (net (code "176") (name "VCCIO") (class "Default")
      (node (ref "C80") (pin "1") (pinfunction "1_1") (pintype "passive"))
      (node (ref "R212") (pin "2") (pinfunction "2_2") (pintype "passive"))
      (node (ref "R45") (pin "1") (pinfunction "1_1") (pintype "passive"))
      (node (ref "R46") (pin "1") (pinfunction "1_1") (pintype "passive"))
      (node (ref "U17") (pin "8") (pinfunction "VCC_8") (pintype "power_in"))
    )
    (net (code "177") (name "unconnected-(R184-Pad4A)") (class "Default")
      (node (ref "R184") (pin "4A") (pinfunction "4A_4A") (pintype "passive"))
    )
    (net (code "178") (name "unconnected-(R184-Pad4B)") (class "Default")
      (node (ref "R184") (pin "4B") (pinfunction "4B_4B") (pintype "passive"))
    )
  )
)
